# IO.net
KiCad netlist of a schematic drawn in Altium Designer
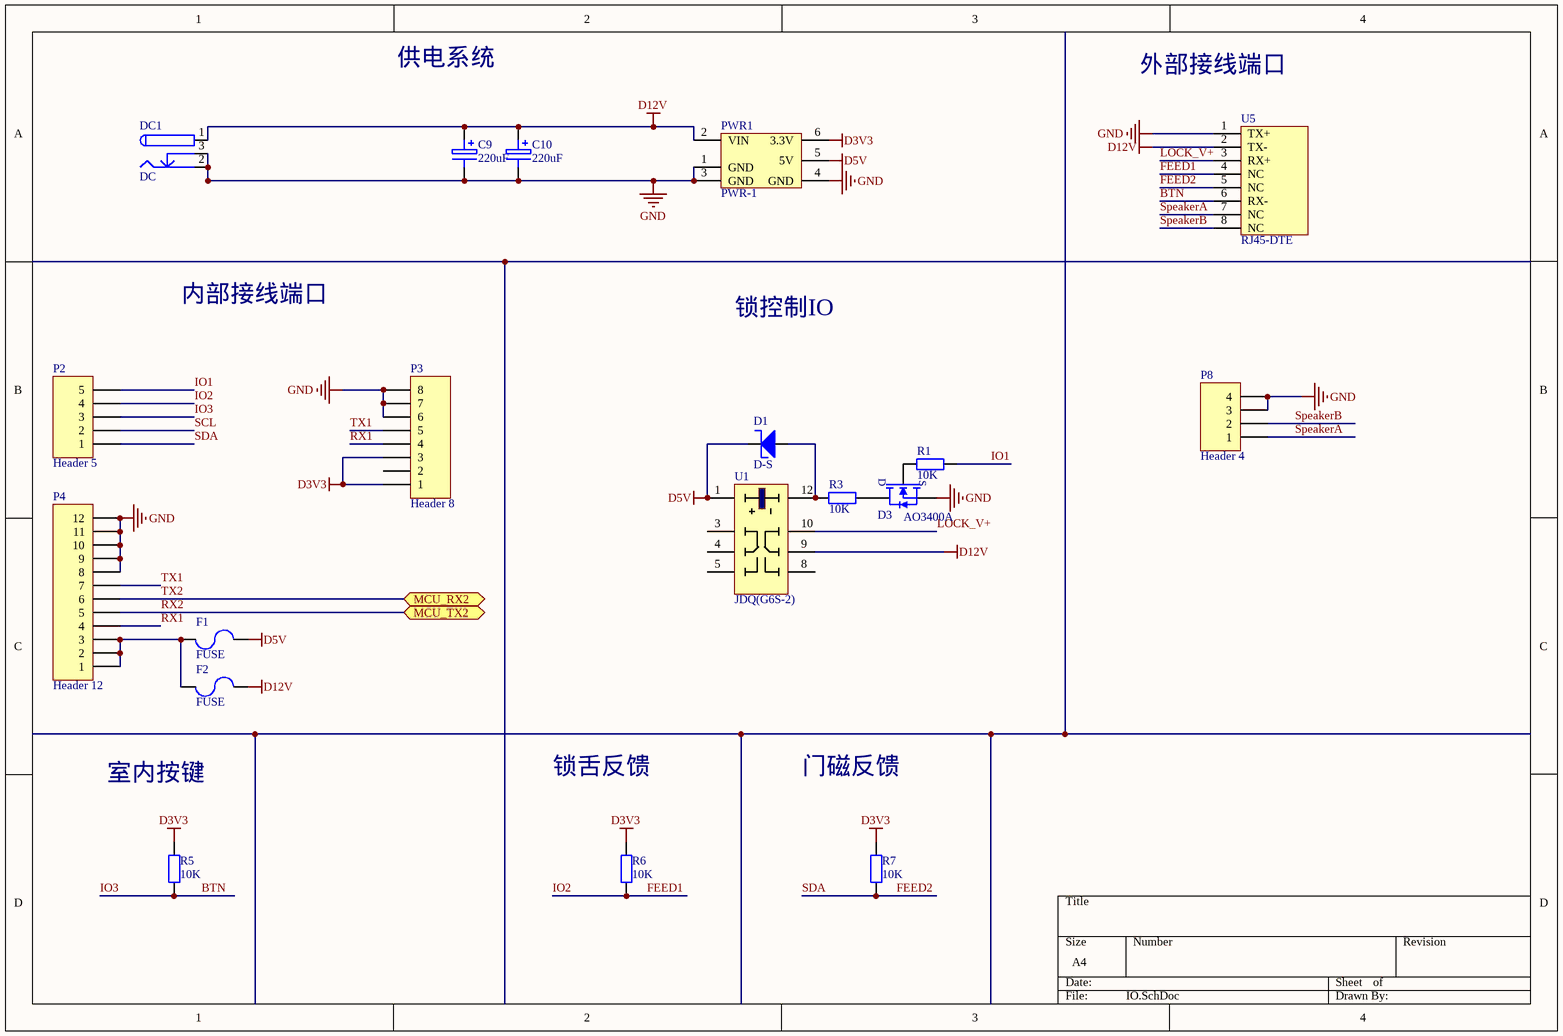
[diagram p0: IO.SchDoc]

(export (version "E")
  (design (tool "Eeschema 10.0.6"))
  (components
    (comp (ref "C9")
      (value "220uF")
      (footprint "RB.2/.4")
      (description "电解电容")
      (libsource (lib "lib_AD") (part "CAP-E"))
    )
    (comp (ref "C10")
      (value "220uF")
      (footprint "RB.2/.4")
      (description "电解电容")
      (libsource (lib "lib_AD") (part "CAP-E"))
    )
    (comp (ref "D1")
      (value "D-S")
      (footprint "DO-214AC(SMA)")
      (description "肖特基二极管")
      (libsource (lib "lib_AD") (part "D-S"))
    )
    (comp (ref "D3")
      (value "AO3400A")
      (footprint "SOT23A")
      (description "NMOS")
      (libsource (lib "lib_AD") (part "MOS-N"))
    )
    (comp (ref "DC1")
      (value "DC")
      (footprint "DC005")
      (description "圆形电源接口")
      (libsource (lib "lib_AD") (part "DC00X"))
    )
    (comp (ref "F1")
      (value "FUSE")
      (footprint "0805F")
      (description "CR-1812-050A60V")
      (libsource (lib "lib_AD") (part "FUSE"))
    )
    (comp (ref "F2")
      (value "FUSE")
      (footprint "0805F")
      (description "CR-1812-050A60V")
      (libsource (lib "lib_AD") (part "FUSE"))
    )
    (comp (ref "P2")
      (value "Header 5")
      (footprint "XH2.54-5")
      (description "Header, 5-Pin")
      (fields (field (name "PUBLISHER") "Altium Limited"))
      (libsource (lib "lib_AD") (part "Header 5"))
    )
    (comp (ref "P3")
      (value "Header 8")
      (footprint "FPC/1.25T-6P")
      (description "Header, 8-Pin")
      (fields (field (name "PUBLISHER") "Altium Limited"))
      (libsource (lib "lib_AD") (part "Header 8"))
    )
    (comp (ref "P4")
      (value "Header 12")
      (footprint "FFC/SM1.0-2H10")
      (description "Header, 12-Pin")
      (fields (field (name "PUBLISHER") "Altium Limited"))
      (libsource (lib "lib_AD") (part "Header 12"))
    )
    (comp (ref "P8")
      (value "Header 4")
      (footprint "FPC/1.25T-2P")
      (description "Header, 4-Pin")
      (fields (field (name "PUBLISHER") "Altium Limited"))
      (libsource (lib "lib_AD") (part "Header 4"))
    )
    (comp (ref "PWR1") (value "PWR-1") (footprint "PWR-1") (libsource (lib "lib_AD") (part "PWR-1")))
    (comp (ref "R1")
      (value "10K")
      (footprint "0603R")
      (description "普通电阻")
      (libsource (lib "lib_AD") (part "RES"))
    )
    (comp (ref "R3")
      (value "10K")
      (footprint "0603R")
      (description "普通电阻")
      (libsource (lib "lib_AD") (part "RES"))
    )
    (comp (ref "R5")
      (value "10K")
      (footprint "0603R")
      (description "普通电阻")
      (libsource (lib "") (part "RES_1"))
    )
    (comp (ref "R6")
      (value "10K")
      (footprint "0603R")
      (description "普通电阻")
      (libsource (lib "") (part "RES_1"))
    )
    (comp (ref "R7")
      (value "10K")
      (footprint "0603R")
      (description "普通电阻")
      (libsource (lib "") (part "RES_1"))
    )
    (comp (ref "U1")
      (value "JDQ(G6S-2)")
      (footprint "JDQ-G6S-2")
      (description "继电器（G6S-2 5VDC）")
      (libsource (lib "lib_AD") (part "JDQ(G6S-2)"))
    )
    (comp (ref "U5")
      (value "RJ45-DTE")
      (footprint "RJ45-2")
      (description "设备")
      (libsource (lib "lib_AD") (part "RJ45-DTE"))
    )
  )
  (nets
    (net (code "1") (name "/BTN") (class "Default")
      (node (ref "P2") (pin "3") (pinfunction "3_3") (pintype "passive"))
      (node (ref "R5") (pin "1") (pinfunction "1_1") (pintype "passive"))
      (node (ref "U5") (pin "6") (pinfunction "RX-_6") (pintype "passive"))
    )
    (net (code "2") (name "/FEED1") (class "Default")
      (node (ref "P2") (pin "4") (pinfunction "4_4") (pintype "passive"))
      (node (ref "R6") (pin "1") (pinfunction "1_1") (pintype "passive"))
      (node (ref "U5") (pin "4") (pinfunction "NC_4") (pintype "passive"))
    )
    (net (code "3") (name "/FEED2") (class "Default")
      (node (ref "P2") (pin "1") (pinfunction "1_1") (pintype "passive"))
      (node (ref "R7") (pin "1") (pinfunction "1_1") (pintype "passive"))
      (node (ref "U5") (pin "5") (pinfunction "NC_5") (pintype "passive"))
    )
    (net (code "4") (name "/IO1") (class "Default")
      (node (ref "P2") (pin "5") (pinfunction "5_5") (pintype "passive"))
      (node (ref "R1") (pin "2") (pinfunction "2_2") (pintype "passive"))
    )
    (net (code "5") (name "/LOCK_V+") (class "Default")
      (node (ref "U1") (pin "10") (pinfunction "10_10") (pintype "passive"))
      (node (ref "U5") (pin "3") (pinfunction "RX+_3") (pintype "passive"))
    )
    (net (code "6") (name "/RX1") (class "Default")
      (node (ref "P3") (pin "4") (pinfunction "4_4") (pintype "passive"))
      (node (ref "P4") (pin "4") (pinfunction "4_4") (pintype "passive"))
    )
    (net (code "7") (name "/RX2") (class "Default")
      (node (ref "P4") (pin "5") (pinfunction "5_5") (pintype "passive"))
    )
    (net (code "8") (name "/SCL") (class "Default")
      (node (ref "P2") (pin "2") (pinfunction "2_2") (pintype "passive"))
    )
    (net (code "9") (name "/SpeakerA") (class "Default")
      (node (ref "P8") (pin "1") (pinfunction "1_1") (pintype "passive"))
      (node (ref "U5") (pin "7") (pinfunction "NC_7") (pintype "passive"))
    )
    (net (code "10") (name "/SpeakerB") (class "Default")
      (node (ref "P8") (pin "2") (pinfunction "2_2") (pintype "passive"))
      (node (ref "U5") (pin "8") (pinfunction "NC_8") (pintype "passive"))
    )
    (net (code "11") (name "/TX1") (class "Default")
      (node (ref "P3") (pin "5") (pinfunction "5_5") (pintype "passive"))
      (node (ref "P4") (pin "7") (pinfunction "7_7") (pintype "passive"))
    )
    (net (code "12") (name "/TX2") (class "Default")
      (node (ref "P4") (pin "6") (pinfunction "6_6") (pintype "passive"))
    )
    (net (code "13") (name "D3V3") (class "Default")
      (node (ref "P3") (pin "1") (pinfunction "1_1") (pintype "passive"))
      (node (ref "P3") (pin "3") (pinfunction "3_3") (pintype "passive"))
      (node (ref "PWR1") (pin "6") (pinfunction "3.3V_6") (pintype "passive"))
      (node (ref "R5") (pin "2") (pinfunction "2_2") (pintype "passive"))
      (node (ref "R6") (pin "2") (pinfunction "2_2") (pintype "passive"))
      (node (ref "R7") (pin "2") (pinfunction "2_2") (pintype "passive"))
    )
    (net (code "14") (name "D5V") (class "Default")
      (node (ref "D1") (pin "K") (pinfunction "2_K") (pintype "passive"))
      (node (ref "F1") (pin "1") (pinfunction "1_1") (pintype "passive"))
      (node (ref "PWR1") (pin "5") (pinfunction "5V_5") (pintype "passive"))
      (node (ref "U1") (pin "1") (pinfunction "1_1") (pintype "passive"))
    )
    (net (code "15") (name "D12V") (class "Default")
      (node (ref "C10") (pin "1") (pinfunction "1_1") (pintype "passive"))
      (node (ref "C9") (pin "1") (pinfunction "1_1") (pintype "passive"))
      (node (ref "DC1") (pin "1") (pinfunction "1_1") (pintype "power_in"))
      (node (ref "F2") (pin "1") (pinfunction "1_1") (pintype "passive"))
      (node (ref "PWR1") (pin "2") (pinfunction "VIN_2") (pintype "passive"))
      (node (ref "U1") (pin "9") (pinfunction "9_9") (pintype "passive"))
      (node (ref "U5") (pin "2") (pinfunction "TX-_2") (pintype "passive"))
    )
    (net (code "16") (name "GND") (class "Default")
      (node (ref "C10") (pin "2") (pinfunction "2_2") (pintype "passive"))
      (node (ref "C9") (pin "2") (pinfunction "2_2") (pintype "passive"))
      (node (ref "D3") (pin "2") (pinfunction "S_2") (pintype "passive"))
      (node (ref "DC1") (pin "2") (pinfunction "2_2") (pintype "power_in"))
      (node (ref "DC1") (pin "3") (pinfunction "3_3") (pintype "power_in"))
      (node (ref "P3") (pin "6") (pinfunction "6_6") (pintype "passive"))
      (node (ref "P3") (pin "7") (pinfunction "7_7") (pintype "passive"))
      (node (ref "P3") (pin "8") (pinfunction "8_8") (pintype "passive"))
      (node (ref "P4") (pin "10") (pinfunction "10_10") (pintype "passive"))
      (node (ref "P4") (pin "11") (pinfunction "11_11") (pintype "passive"))
      (node (ref "P4") (pin "12") (pinfunction "12_12") (pintype "passive"))
      (node (ref "P4") (pin "8") (pinfunction "8_8") (pintype "passive"))
      (node (ref "P4") (pin "9") (pinfunction "9_9") (pintype "passive"))
      (node (ref "P8") (pin "3") (pinfunction "3_3") (pintype "passive"))
      (node (ref "P8") (pin "4") (pinfunction "4_4") (pintype "passive"))
      (node (ref "PWR1") (pin "1") (pinfunction "GND_1") (pintype "passive"))
      (node (ref "PWR1") (pin "3") (pinfunction "GND_3") (pintype "passive"))
      (node (ref "PWR1") (pin "4") (pinfunction "GND_4") (pintype "passive"))
      (node (ref "U5") (pin "1") (pinfunction "TX+_1") (pintype "passive"))
    )
    (net (code "17") (name "Net-(D1-1)") (class "Default")
      (node (ref "D1") (pin "A") (pinfunction "1_A") (pintype "passive"))
      (node (ref "R3") (pin "1") (pinfunction "1_1") (pintype "passive"))
      (node (ref "U1") (pin "12") (pinfunction "12_12") (pintype "passive"))
    )
    (net (code "18") (name "Net-(D3-D)") (class "Default")
      (node (ref "D3") (pin "3") (pinfunction "D_3") (pintype "passive"))
      (node (ref "R3") (pin "2") (pinfunction "2_2") (pintype "passive"))
    )
    (net (code "19") (name "Net-(D3-G)") (class "Default")
      (node (ref "D3") (pin "1") (pinfunction "G_1") (pintype "passive"))
      (node (ref "R1") (pin "1") (pinfunction "1_1") (pintype "passive"))
    )
    (net (code "20") (name "Net-(F1-Pad2)") (class "Default")
      (node (ref "F1") (pin "2") (pinfunction "2_2") (pintype "passive"))
      (node (ref "F2") (pin "2") (pinfunction "2_2") (pintype "passive"))
      (node (ref "P4") (pin "1") (pinfunction "1_1") (pintype "passive"))
      (node (ref "P4") (pin "2") (pinfunction "2_2") (pintype "passive"))
      (node (ref "P4") (pin "3") (pinfunction "3_3") (pintype "passive"))
    )
    (net (code "21") (name "unconnected-(P3-Pad2)") (class "Default")
      (node (ref "P3") (pin "2") (pinfunction "2_2") (pintype "passive"))
    )
    (net (code "22") (name "unconnected-(U1-Pad3)") (class "Default")
      (node (ref "U1") (pin "3") (pinfunction "3_3") (pintype "passive"))
    )
    (net (code "23") (name "unconnected-(U1-Pad4)") (class "Default")
      (node (ref "U1") (pin "4") (pinfunction "4_4") (pintype "passive"))
    )
    (net (code "24") (name "unconnected-(U1-Pad5)") (class "Default")
      (node (ref "U1") (pin "5") (pinfunction "5_5") (pintype "passive"))
    )
    (net (code "25") (name "unconnected-(U1-Pad8)") (class "Default")
      (node (ref "U1") (pin "8") (pinfunction "8_8") (pintype "passive"))
    )
  )
)
